# USB.net
KiCad netlist of a schematic drawn in Altium Designer
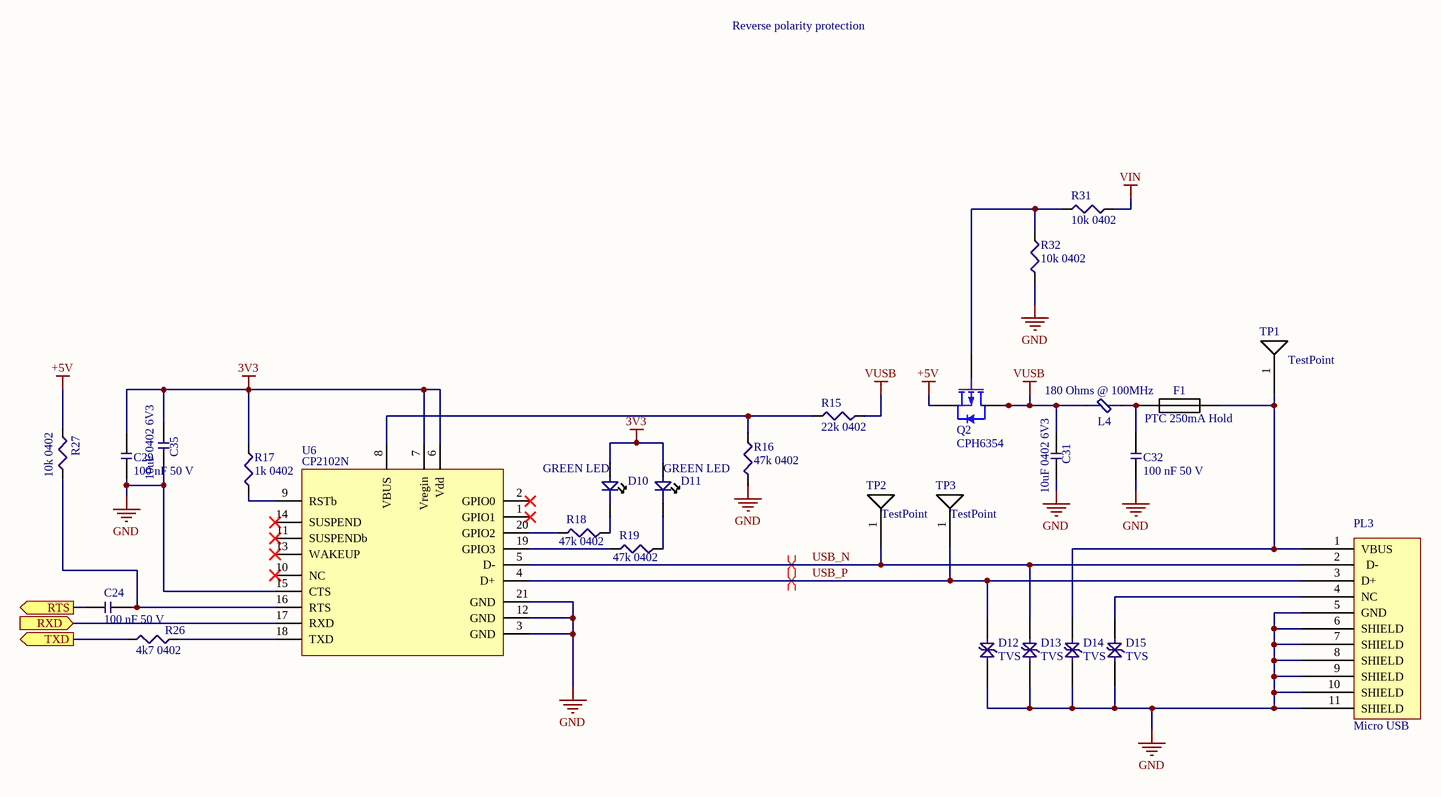
[diagram p0: USB.SchDoc]

(export (version "E")
  (design (tool "Eeschema 10.0.6"))
  (components
    (comp (ref "C24")
      (value "100 nF 50 V")
      (footprint "CAP_0402")
      (description "Multilayer Ceramic Capacitors MLCC - SMD/SMT .1uF 50Volts X7R +/-10% 0402 STD")
      (fields (field (name "TOLERANCE") "10%") (field (name "VOLTAGE") "50 V"))
      (libsource (lib "ON Development Vault") (part "Capacitor"))
    )
    (comp (ref "C29")
      (value "100 nF 50 V")
      (footprint "CAP_0402")
      (description "Multilayer Ceramic Capacitors MLCC - SMD/SMT .1uF 50Volts X7R +/-10% 0402 STD")
      (fields (field (name "TOLERANCE") "10%") (field (name "VOLTAGE") "50 V"))
      (libsource (lib "ON Development Vault") (part "Capacitor"))
    )
    (comp (ref "C31")
      (value "10uF 0402 6V3")
      (footprint "CAP_0402")
      (description "10uF 20% 0402 6V3 X6S")
      (fields (field (name "TOLERANCE") "20%") (field (name "VOLTAGE") "6V3"))
      (libsource (lib "ON Development Vault") (part "Capacitor"))
    )
    (comp (ref "C32")
      (value "100 nF 50 V")
      (footprint "CAP_0402")
      (description "Multilayer Ceramic Capacitors MLCC - SMD/SMT .1uF 50Volts X7R +/-10% 0402 STD")
      (fields (field (name "TOLERANCE") "10%") (field (name "VOLTAGE") "50 V"))
      (libsource (lib "ON Development Vault") (part "Capacitor"))
    )
    (comp (ref "C35")
      (value "10uF 0402 6V3")
      (footprint "CAP_0402")
      (description "10uF 20% 0402 6V3 X6S")
      (fields (field (name "TOLERANCE") "20%") (field (name "VOLTAGE") "6V3"))
      (libsource (lib "ON Development Vault") (part "Capacitor"))
    )
    (comp (ref "D10")
      (value "GREEN LED")
      (footprint "0402 LED")
      (description "0402 SMD LED")
      (fields (field (name "MFG. PART NUMBER") "LTST-C281KGKT"))
      (libsource (lib "ON Development Vault") (part "LED"))
    )
    (comp (ref "D11")
      (value "GREEN LED")
      (footprint "0402 LED")
      (description "0402 SMD LED")
      (fields (field (name "MFG. PART NUMBER") "LTST-C281KGKT"))
      (libsource (lib "ON Development Vault") (part "LED"))
    )
    (comp (ref "D12")
      (value "TVS")
      (footprint "RES_0402")
      (description "TVS DIODE 12VC 8A IPP 0402")
      (fields (field (name "MFG. PART NUMBER") "GG040205100N2P"))
      (libsource (lib "ON Development Vault") (part "TVS"))
    )
    (comp (ref "D13")
      (value "TVS")
      (footprint "RES_0402")
      (description "TVS DIODE 12VC 8A IPP 0402")
      (fields (field (name "MFG. PART NUMBER") "GG040205100N2P"))
      (libsource (lib "ON Development Vault") (part "TVS"))
    )
    (comp (ref "D14")
      (value "TVS")
      (footprint "RES_0402")
      (description "TVS DIODE 12VC 8A IPP 0402")
      (fields (field (name "MFG. PART NUMBER") "GG040205100N2P"))
      (libsource (lib "ON Development Vault") (part "TVS"))
    )
    (comp (ref "D15")
      (value "TVS")
      (footprint "RES_0402")
      (description "TVS DIODE 12VC 8A IPP 0402")
      (fields (field (name "MFG. PART NUMBER") "GG040205100N2P"))
      (libsource (lib "ON Development Vault") (part "TVS"))
    )
    (comp (ref "F1")
      (value "PTC 250mA Hold")
      (footprint "PTC Fuse 1206")
      (description "PTC RESET FUSE 24V 250MA 1206")
      (fields (field (name "MFG. PART NUMBER") "0ZCJ0025AF2E"))
      (libsource (lib "ON Development Vault") (part "Fuse"))
    )
    (comp (ref "L4")
      (value "180 Ohms @ 100MHz")
      (footprint "IND_0603")
      (description "FERRITE BEAD 180 OHM 0603 1LN")
      (fields (field (name "MFG. PART NUMBER") "BLM18PG181SN1D"))
      (libsource (lib "ON Development Vault") (part "Ferrite"))
    )
    (comp (ref "PL3")
      (value "Micro USB")
      (footprint "10118193-0001LF Micro USB")
      (description "CONN USB MICRO B RECPT SMT R/A")
      (fields (field (name "MFG. PART NUMBER") "10118193-0001LF"))
      (libsource (lib "ON Development Vault") (part "USB 2.0 Micro usb type B header"))
    )
    (comp (ref "Q2")
      (value "CPH6354")
      (footprint "SOT95P280X95-6N")
      (description "MOSFET P-CH 60V 4A CPH6")
      (fields (field (name "MFG. PART NUMBER") "CPH6354-TL-W"))
      (libsource (lib "ON Development Vault") (part "P-channel CPH6354"))
    )
    (comp (ref "R15")
      (value "22k 0402")
      (footprint "RES_0402")
      (description "RES SMD 22K OHM 1% 1/16W 0402")
      (fields (field (name "POWER") "1/16W") (field (name "TOLERANCE") "1%"))
      (libsource (lib "ON Development Vault") (part "Resistor"))
    )
    (comp (ref "R16")
      (value "47k 0402")
      (footprint "RES_0402")
      (description "RES SMD 47K OHM 1% 1/16W 0402")
      (fields (field (name "POWER") "1/16W") (field (name "TOLERANCE") "1%"))
      (libsource (lib "ON Development Vault") (part "Resistor"))
    )
    (comp (ref "R17")
      (value "1k 0402")
      (footprint "RES_0402")
      (description "RES SMD 1K OHM 1% 1/16W 0402")
      (fields (field (name "POWER") "1/16W") (field (name "TOLERANCE") "1%"))
      (libsource (lib "ON Development Vault") (part "Resistor"))
    )
    (comp (ref "R18")
      (value "47k 0402")
      (footprint "RES_0402")
      (description "RES SMD 47K OHM 1% 1/16W 0402")
      (fields (field (name "POWER") "1/16W") (field (name "TOLERANCE") "1%"))
      (libsource (lib "ON Development Vault") (part "Resistor"))
    )
    (comp (ref "R19")
      (value "47k 0402")
      (footprint "RES_0402")
      (description "RES SMD 47K OHM 1% 1/16W 0402")
      (fields (field (name "POWER") "1/16W") (field (name "TOLERANCE") "1%"))
      (libsource (lib "ON Development Vault") (part "Resistor"))
    )
    (comp (ref "R26")
      (value "4k7 0402")
      (footprint "RES_0402")
      (description "RES SMD 4.7K OHM 1% 1/16W 0402")
      (fields (field (name "POWER") "1/16W") (field (name "TOLERANCE") "1"))
      (libsource (lib "ON Development Vault") (part "Resistor"))
    )
    (comp (ref "R27")
      (value "10k 0402")
      (footprint "RES_0402")
      (description "RES SMD 10K OHM 1% 1/16W 0402")
      (fields (field (name "POWER") "1/16 W") (field (name "TOLERANCE") "1 %"))
      (libsource (lib "ON Development Vault") (part "Resistor"))
    )
    (comp (ref "R31")
      (value "10k 0402")
      (footprint "RES_0402")
      (description "RES SMD 10K OHM 1% 1/16W 0402")
      (fields (field (name "POWER") "1/16 W") (field (name "TOLERANCE") "1 %"))
      (libsource (lib "ON Development Vault") (part "Resistor"))
    )
    (comp (ref "R32")
      (value "10k 0402")
      (footprint "RES_0402")
      (description "RES SMD 10K OHM 1% 1/16W 0402")
      (fields (field (name "POWER") "1/16 W") (field (name "TOLERANCE") "1 %"))
      (libsource (lib "ON Development Vault") (part "Resistor"))
    )
    (comp (ref "TP1")
      (value "TestPoint")
      (footprint "1x0mm")
      (description "Testpoint")
      (libsource (lib "ON Development Vault") (part "CMP-ROOT-0006-0.0"))
    )
    (comp (ref "TP2")
      (value "TestPoint")
      (footprint "1x0mm")
      (description "Testpoint")
      (libsource (lib "ON Development Vault") (part "CMP-ROOT-0006-0.0"))
    )
    (comp (ref "TP3")
      (value "TestPoint")
      (footprint "1x0mm")
      (description "Testpoint")
      (libsource (lib "ON Development Vault") (part "CMP-ROOT-0006-0.0"))
    )
    (comp (ref "U6")
      (value "CP2102N")
      (footprint "QFN50P300X300X80_HS-21N")
      (description "IC BRIDGE USB TO UART 20QFN")
      (fields (field (name "MFG. PART NUMBER") "CP2102N-A01-GQFN20"))
      (libsource (lib "ON Development Vault") (part "CP2102N-A01-GQFN20"))
    )
  )
  (nets
    (net (code "1") (name "+5V") (class "Default")
      (node (ref "Q2") (pin "4") (pinfunction "SOURCE_4") (pintype "passive"))
      (node (ref "R27") (pin "2") (pinfunction "2_2") (pintype "passive"))
    )
    (net (code "2") (name "/RTS") (class "Default")
      (node (ref "C24") (pin "1") (pinfunction "1_1") (pintype "passive"))
    )
    (net (code "3") (name "/RXD") (class "Default")
      (node (ref "U6") (pin "17") (pinfunction "RXD_17") (pintype "passive"))
    )
    (net (code "4") (name "/TXD") (class "Default")
      (node (ref "R26") (pin "2") (pinfunction "2_2") (pintype "passive"))
    )
    (net (code "5") (name "/USB_N") (class "Default")
      (node (ref "D13") (pin "2") (pinfunction "Cathode_2") (pintype "passive"))
      (node (ref "PL3") (pin "2") (pinfunction "D-_2") (pintype "passive"))
      (node (ref "TP2") (pin "1") (pinfunction "0_1") (pintype "passive"))
      (node (ref "U6") (pin "5") (pinfunction "D-_5") (pintype "passive"))
    )
    (net (code "6") (name "/USB_P") (class "Default")
      (node (ref "D12") (pin "2") (pinfunction "Cathode_2") (pintype "passive"))
      (node (ref "PL3") (pin "3") (pinfunction "D+_3") (pintype "passive"))
      (node (ref "TP3") (pin "1") (pinfunction "0_1") (pintype "passive"))
      (node (ref "U6") (pin "4") (pinfunction "D+_4") (pintype "passive"))
    )
    (net (code "7") (name "3V3") (class "Default")
      (node (ref "C29") (pin "1") (pinfunction "1_1") (pintype "passive"))
      (node (ref "C35") (pin "2") (pinfunction "2_2") (pintype "passive"))
      (node (ref "D10") (pin "1") (pinfunction "1_1") (pintype "passive"))
      (node (ref "D11") (pin "1") (pinfunction "1_1") (pintype "passive"))
      (node (ref "R17") (pin "2") (pinfunction "2_2") (pintype "passive"))
      (node (ref "U6") (pin "6") (pinfunction "Vdd_6") (pintype "passive"))
      (node (ref "U6") (pin "7") (pinfunction "Vregin_7") (pintype "passive"))
    )
    (net (code "8") (name "GND") (class "Default")
      (node (ref "C29") (pin "2") (pinfunction "2_2") (pintype "passive"))
      (node (ref "C31") (pin "1") (pinfunction "1_1") (pintype "passive"))
      (node (ref "C32") (pin "2") (pinfunction "2_2") (pintype "passive"))
      (node (ref "C35") (pin "1") (pinfunction "1_1") (pintype "passive"))
      (node (ref "D12") (pin "1") (pinfunction "Anode_1") (pintype "passive"))
      (node (ref "D13") (pin "1") (pinfunction "Anode_1") (pintype "passive"))
      (node (ref "D14") (pin "1") (pinfunction "Anode_1") (pintype "passive"))
      (node (ref "D15") (pin "1") (pinfunction "Anode_1") (pintype "passive"))
      (node (ref "PL3") (pin "10") (pinfunction "SHIELD_10") (pintype "passive"))
      (node (ref "PL3") (pin "11") (pinfunction "SHIELD_11") (pintype "passive"))
      (node (ref "PL3") (pin "5") (pinfunction "GND_5") (pintype "passive"))
      (node (ref "PL3") (pin "6") (pinfunction "SHIELD_6") (pintype "passive"))
      (node (ref "PL3") (pin "7") (pinfunction "SHIELD_7") (pintype "passive"))
      (node (ref "PL3") (pin "8") (pinfunction "SHIELD_8") (pintype "passive"))
      (node (ref "PL3") (pin "9") (pinfunction "SHIELD_9") (pintype "passive"))
      (node (ref "R16") (pin "1") (pinfunction "1_1") (pintype "passive"))
      (node (ref "R32") (pin "2") (pinfunction "2_2") (pintype "passive"))
      (node (ref "U6") (pin "12") (pinfunction "GND_12") (pintype "passive"))
      (node (ref "U6") (pin "15") (pinfunction "CTS_15") (pintype "passive"))
      (node (ref "U6") (pin "21") (pinfunction "GND_21") (pintype "passive"))
      (node (ref "U6") (pin "3") (pinfunction "GND_3") (pintype "passive"))
    )
    (net (code "9") (name "Net-(C32-Pad1)") (class "Default")
      (node (ref "C32") (pin "1") (pinfunction "1_1") (pintype "passive"))
      (node (ref "F1") (pin "1") (pinfunction "1_1") (pintype "passive"))
      (node (ref "L4") (pin "2") (pinfunction "2_2") (pintype "passive"))
    )
    (net (code "10") (name "Net-(D10-Pad2)") (class "Default")
      (node (ref "D10") (pin "2") (pinfunction "2_2") (pintype "passive"))
      (node (ref "R18") (pin "1") (pinfunction "1_1") (pintype "passive"))
    )
    (net (code "11") (name "Net-(D11-Pad2)") (class "Default")
      (node (ref "D11") (pin "2") (pinfunction "2_2") (pintype "passive"))
      (node (ref "R19") (pin "1") (pinfunction "1_1") (pintype "passive"))
    )
    (net (code "12") (name "Net-(D14-Cathode)") (class "Default")
      (node (ref "D14") (pin "2") (pinfunction "Cathode_2") (pintype "passive"))
      (node (ref "F1") (pin "2") (pinfunction "2_2") (pintype "passive"))
      (node (ref "PL3") (pin "1") (pinfunction "VBUS_1") (pintype "passive"))
      (node (ref "TP1") (pin "1") (pinfunction "0_1") (pintype "passive"))
    )
    (net (code "13") (name "Net-(D15-Cathode)") (class "Default")
      (node (ref "D15") (pin "2") (pinfunction "Cathode_2") (pintype "passive"))
      (node (ref "PL3") (pin "4") (pinfunction "NC_4") (pintype "passive"))
    )
    (net (code "14") (name "Net-(Q2-GATE)") (class "Default")
      (node (ref "Q2") (pin "3") (pinfunction "GATE_3") (pintype "passive"))
      (node (ref "R31") (pin "2") (pinfunction "2_2") (pintype "passive"))
      (node (ref "R32") (pin "1") (pinfunction "1_1") (pintype "passive"))
    )
    (net (code "15") (name "Net-(U6-GPIO2)") (class "Default")
      (node (ref "R18") (pin "2") (pinfunction "2_2") (pintype "passive"))
      (node (ref "U6") (pin "20") (pinfunction "GPIO2_20") (pintype "passive"))
    )
    (net (code "16") (name "Net-(U6-GPIO3)") (class "Default")
      (node (ref "R19") (pin "2") (pinfunction "2_2") (pintype "passive"))
      (node (ref "U6") (pin "19") (pinfunction "GPIO3_19") (pintype "passive"))
    )
    (net (code "17") (name "Net-(U6-RSTb)") (class "Default")
      (node (ref "R17") (pin "1") (pinfunction "1_1") (pintype "passive"))
      (node (ref "U6") (pin "9") (pinfunction "RSTb_9") (pintype "passive"))
    )
    (net (code "18") (name "Net-(U6-RTS)") (class "Default")
      (node (ref "C24") (pin "2") (pinfunction "2_2") (pintype "passive"))
      (node (ref "R27") (pin "1") (pinfunction "1_1") (pintype "passive"))
      (node (ref "U6") (pin "16") (pinfunction "RTS_16") (pintype "passive"))
    )
    (net (code "19") (name "Net-(U6-TXD)") (class "Default")
      (node (ref "R26") (pin "1") (pinfunction "1_1") (pintype "passive"))
      (node (ref "U6") (pin "18") (pinfunction "TXD_18") (pintype "passive"))
    )
    (net (code "20") (name "Net-(U6-VBUS)") (class "Default")
      (node (ref "R15") (pin "1") (pinfunction "1_1") (pintype "passive"))
      (node (ref "R16") (pin "2") (pinfunction "2_2") (pintype "passive"))
      (node (ref "U6") (pin "8") (pinfunction "VBUS_8") (pintype "passive"))
    )
    (net (code "21") (name "VIN") (class "Default")
      (node (ref "R31") (pin "1") (pinfunction "1_1") (pintype "passive"))
    )
    (net (code "22") (name "VUSB") (class "Default")
      (node (ref "C31") (pin "2") (pinfunction "2_2") (pintype "passive"))
      (node (ref "L4") (pin "1") (pinfunction "1_1") (pintype "passive"))
      (node (ref "Q2") (pin "1") (pinfunction "DRAIN_1") (pintype "passive"))
      (node (ref "Q2") (pin "2") (pinfunction "DRAIN_2") (pintype "passive"))
      (node (ref "Q2") (pin "5") (pinfunction "DRAIN_5") (pintype "passive"))
      (node (ref "Q2") (pin "6") (pinfunction "DRAIN_6") (pintype "passive"))
      (node (ref "R15") (pin "2") (pinfunction "2_2") (pintype "passive"))
    )
    (net (code "23") (name "unconnected-(U6-GPIO0-Pad2)") (class "Default")
      (node (ref "U6") (pin "2") (pinfunction "GPIO0_2") (pintype "passive+no_connect"))
    )
    (net (code "24") (name "unconnected-(U6-GPIO1-Pad1)") (class "Default")
      (node (ref "U6") (pin "1") (pinfunction "GPIO1_1") (pintype "passive+no_connect"))
    )
    (net (code "25") (name "unconnected-(U6-NC-Pad10)") (class "Default")
      (node (ref "U6") (pin "10") (pinfunction "NC_10") (pintype "passive+no_connect"))
    )
    (net (code "26") (name "unconnected-(U6-SUSPEND-Pad14)") (class "Default")
      (node (ref "U6") (pin "14") (pinfunction "SUSPEND_14") (pintype "passive+no_connect"))
    )
    (net (code "27") (name "unconnected-(U6-SUSPENDb-Pad11)") (class "Default")
      (node (ref "U6") (pin "11") (pinfunction "SUSPENDb_11") (pintype "passive+no_connect"))
    )
    (net (code "28") (name "unconnected-(U6-WAKEUP-Pad13)") (class "Default")
      (node (ref "U6") (pin "13") (pinfunction "WAKEUP_13") (pintype "passive+no_connect"))
    )
  )
)
